# PSoC_Connections.net
KiCad netlist of a schematic drawn in Altium Designer
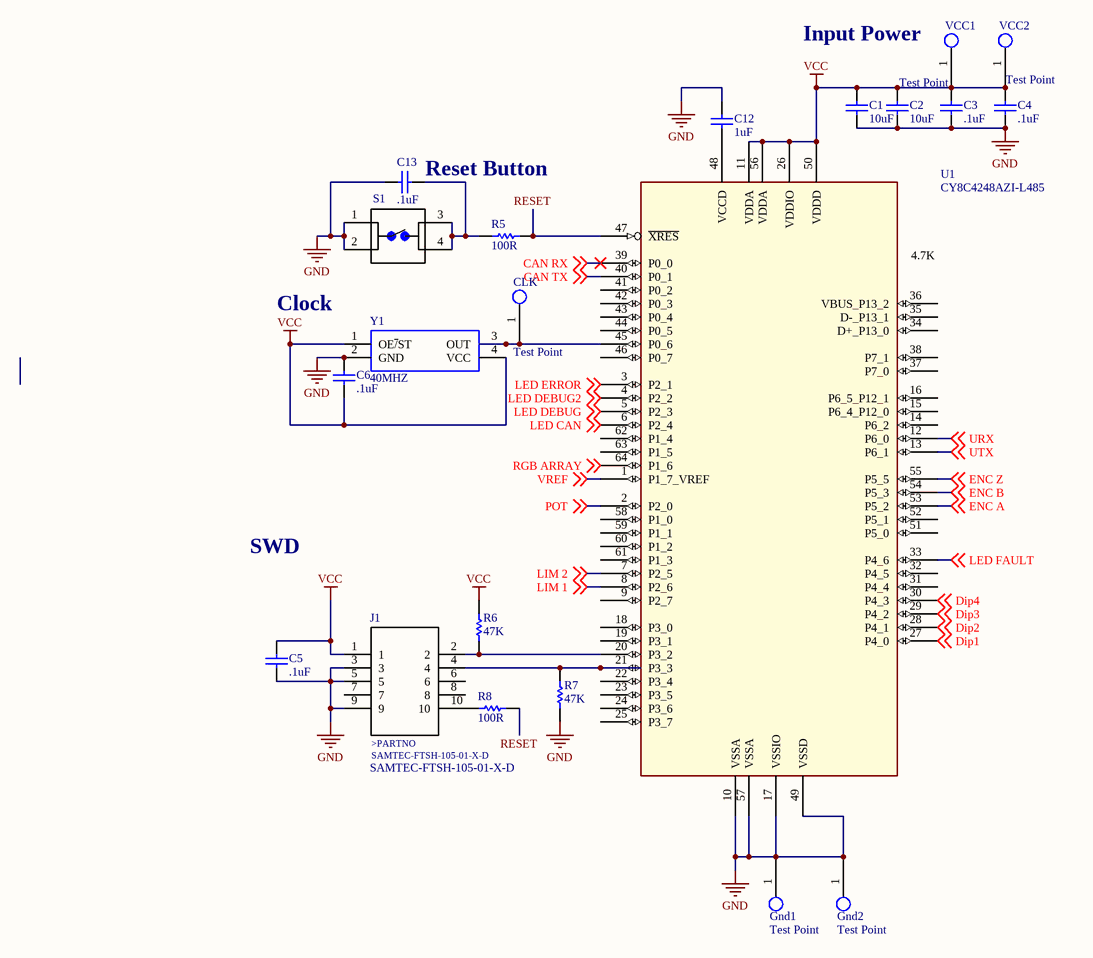
[diagram p0: PSoC Connections.SchDoc]

(export (version "E")
  (design (tool "Eeschema 10.0.6"))
  (components
    (comp (ref "C1")
      (value "10uF")
      (footprint "CAPC0805(2012)130_N")
      (description "CAP 390pF 200V ±5% 0805 (2012 Metric) Thickness 1.3mm SMD")
      (fields (field (name "TOLERANCE") "Â±5%"))
      (libsource (lib "Altium Content Vault") (part "CAP"))
    )
    (comp (ref "C2")
      (value "10uF")
      (footprint "CAPC0805(2012)130_N")
      (description "CAP 390pF 200V ±5% 0805 (2012 Metric) Thickness 1.3mm SMD")
      (fields (field (name "TOLERANCE") "Â±5%"))
      (libsource (lib "Altium Content Vault") (part "CAP"))
    )
    (comp (ref "C3")
      (value ".1uF")
      (footprint "CAPC0805(2012)130_N")
      (description "CAP 390pF 200V ±5% 0805 (2012 Metric) Thickness 1.3mm SMD")
      (fields (field (name "TOLERANCE") "Â±5%"))
      (libsource (lib "Altium Content Vault") (part "CAP"))
    )
    (comp (ref "C4")
      (value ".1uF")
      (footprint "CAPC0805(2012)130_N")
      (description "CAP 390pF 200V ±5% 0805 (2012 Metric) Thickness 1.3mm SMD")
      (fields (field (name "TOLERANCE") "Â±5%"))
      (libsource (lib "Altium Content Vault") (part "CAP"))
    )
    (comp (ref "C5")
      (value ".1uF")
      (footprint "CAPC0805(2012)130_N")
      (description "CAP 390pF 200V ±5% 0805 (2012 Metric) Thickness 1.3mm SMD")
      (fields (field (name "TOLERANCE") "Â±5%"))
      (libsource (lib "Altium Content Vault") (part "CAP"))
    )
    (comp (ref "C6")
      (value ".1uF")
      (footprint "CAPC0805(2012)130_N")
      (description "CAP 390pF 200V ±5% 0805 (2012 Metric) Thickness 1.3mm SMD")
      (fields (field (name "TOLERANCE") "Â±5%"))
      (libsource (lib "Altium Content Vault") (part "CAP"))
    )
    (comp (ref "C12")
      (value "1uF")
      (footprint "CAPC0805(2012)130_N")
      (description "CAP 390pF 200V ±5% 0805 (2012 Metric) Thickness 1.3mm SMD")
      (fields (field (name "TOLERANCE") "Â±5%"))
      (libsource (lib "Altium Content Vault") (part "CAP"))
    )
    (comp (ref "C13")
      (value ".1uF")
      (footprint "CAPC0805(2012)130_N")
      (description "CAP 390pF 200V ±5% 0805 (2012 Metric) Thickness 1.3mm SMD")
      (fields (field (name "TOLERANCE") "Â±5%"))
      (libsource (lib "Altium Content Vault") (part "CAP"))
    )
    (comp (ref "CLK")
      (value "Test Point")
      (footprint "Test Point Through-hole")
      (libsource (lib "Husky Robotics Standard Library 2019-2020") (part "Test Point"))
    )
    (comp (ref "Gnd1")
      (value "Test Point")
      (footprint "Test Point Through-hole")
      (libsource (lib "Husky Robotics Standard Library 2019-2020") (part "Test Point"))
    )
    (comp (ref "Gnd2")
      (value "Test Point")
      (footprint "Test Point Through-hole")
      (libsource (lib "Husky Robotics Standard Library 2019-2020") (part "Test Point"))
    )
    (comp (ref "J1")
      (value "SAMTEC-FTSH-105-01-X-D")
      (footprint "SAMTEC-FTSH-105-01-X-D")
      (libsource (lib "Husky Robotics Standard Library 2019-2020") (part "SAMTEC-FTSH-105-01-X-D"))
    )
    (comp (ref "R5")
      (value "100R")
      (footprint "RESC0805(2012)_N")
      (description "120R 0.125W 5% 0805 (2012 Metric)  SMD")
      (fields (field (name "TOLERANCE") "5 %") (field (name "POWER") "0.125 W"))
      (libsource (lib "Husky Robotics Standard Library 2019-2020") (part "120R 5% 0805"))
    )
    (comp (ref "R6")
      (value "47K")
      (footprint "RESC0805(2012)_N")
      (description "4.7K")
      (fields (field (name "TOLERANCE") "5 %") (field (name "POWER") "0.125 W"))
      (libsource (lib "Husky Robotics Standard Library 2019-2020") (part "120R 5% 0805"))
    )
    (comp (ref "R7")
      (value "47K")
      (footprint "RESC0805(2012)_N")
      (description "120R 0.125W 5% 0805 (2012 Metric)  SMD")
      (fields (field (name "TOLERANCE") "5 %") (field (name "POWER") "0.125 W"))
      (libsource (lib "Husky Robotics Standard Library 2019-2020") (part "120R 5% 0805"))
    )
    (comp (ref "R8")
      (value "100R")
      (footprint "RESC0805(2012)_N")
      (description "120R 0.125W 5% 0805 (2012 Metric)  SMD")
      (fields (field (name "TOLERANCE") "5 %") (field (name "POWER") "0.125 W"))
      (libsource (lib "Husky Robotics Standard Library 2019-2020") (part "120R 5% 0805"))
    )
    (comp (ref "S1")
      (value "1825910-7")
      (footprint "Switch 6mm 24V (NO)")
      (description "FSM4JAH=6MM TACT SWITCH, HIGH TEMP")
      (fields (field (name "MF") "TE Connectivity") (field (name "DIGI-KEY_PART_NUMBER") "450-1804-ND"))
      (libsource (lib "Husky Robotics Standard Library 2019-2020") (part "Switch 6mm 24V (NO)"))
    )
    (comp (ref "U1")
      (value "CY8C4248AZI-L485")
      (footprint "TQFP50P1200X1200X160-64N")
      (libsource (lib "Husky Robotics Standard Library 2019-2020") (part "CY8C4248AZI-L485"))
    )
    (comp (ref "VCC1")
      (value "Test Point")
      (footprint "Test Point Through-hole")
      (libsource (lib "Husky Robotics Standard Library 2019-2020") (part "Test Point"))
    )
    (comp (ref "VCC2")
      (value "Test Point")
      (footprint "Test Point Through-hole")
      (libsource (lib "Husky Robotics Standard Library 2019-2020") (part "Test Point"))
    )
    (comp (ref "Y1")
      (value "40MHZ")
      (footprint "SG-636")
      (description "Standard Clock Oscillators 50MHz 3.3Volt 100ppm -20C +70C")
      (fields (field (name "MANUFACTURER_PART_NUMBER") "SG-636PCW 50.0000MC3: ROHS"))
      (libsource (lib "Husky Robotics Standard Library 2019-2020") (part "SG-636"))
    )
  )
  (nets
    (net (code "1") (name "/RESET") (class "Default")
      (node (ref "R5") (pin "2") (pinfunction "2_2") (pintype "passive"))
      (node (ref "R8") (pin "2") (pinfunction "2_2") (pintype "passive"))
      (node (ref "U1") (pin "47") (pinfunction "~{XRES}_47") (pintype "input"))
    )
    (net (code "2") (name "CAN RX") (class "Default")
      (node (ref "U1") (pin "39") (pinfunction "P0_0_39") (pintype "bidirectional"))
    )
    (net (code "3") (name "CAN TX") (class "Default")
      (node (ref "U1") (pin "40") (pinfunction "P0_1_40") (pintype "bidirectional"))
    )
    (net (code "4") (name "Dip1") (class "Default")
      (node (ref "U1") (pin "27") (pinfunction "P4_0_27") (pintype "bidirectional"))
    )
    (net (code "5") (name "Dip2") (class "Default")
      (node (ref "U1") (pin "28") (pinfunction "P4_1_28") (pintype "bidirectional"))
    )
    (net (code "6") (name "Dip3") (class "Default")
      (node (ref "U1") (pin "29") (pinfunction "P4_2_29") (pintype "bidirectional"))
    )
    (net (code "7") (name "Dip4") (class "Default")
      (node (ref "U1") (pin "30") (pinfunction "P4_3_30") (pintype "bidirectional"))
    )
    (net (code "8") (name "ENC A") (class "Default")
      (node (ref "U1") (pin "53") (pinfunction "P5_2_53") (pintype "bidirectional"))
    )
    (net (code "9") (name "ENC B") (class "Default")
      (node (ref "U1") (pin "54") (pinfunction "P5_3_54") (pintype "bidirectional"))
    )
    (net (code "10") (name "ENC Z") (class "Default")
      (node (ref "U1") (pin "55") (pinfunction "P5_5_55") (pintype "bidirectional"))
    )
    (net (code "11") (name "GND") (class "Default")
      (node (ref "C1") (pin "1") (pinfunction "1_1") (pintype "passive"))
      (node (ref "C12") (pin "2") (pinfunction "2_2") (pintype "passive"))
      (node (ref "C13") (pin "2") (pinfunction "2_2") (pintype "passive"))
      (node (ref "C2") (pin "1") (pinfunction "1_1") (pintype "passive"))
      (node (ref "C3") (pin "1") (pinfunction "1_1") (pintype "passive"))
      (node (ref "C4") (pin "1") (pinfunction "1_1") (pintype "passive"))
      (node (ref "C5") (pin "1") (pinfunction "1_1") (pintype "passive"))
      (node (ref "C6") (pin "2") (pinfunction "2_2") (pintype "passive"))
      (node (ref "Gnd1") (pin "1") (pinfunction "1_1") (pintype "passive"))
      (node (ref "Gnd2") (pin "1") (pinfunction "1_1") (pintype "passive"))
      (node (ref "J1") (pin "3") (pinfunction "3_3") (pintype "passive"))
      (node (ref "J1") (pin "5") (pinfunction "5_5") (pintype "passive"))
      (node (ref "J1") (pin "9") (pinfunction "9_9") (pintype "passive"))
      (node (ref "R7") (pin "1") (pinfunction "1_1") (pintype "passive"))
      (node (ref "S1") (pin "1") (pinfunction "1_1") (pintype "passive"))
      (node (ref "S1") (pin "2") (pinfunction "2_2") (pintype "passive"))
      (node (ref "U1") (pin "10") (pinfunction "VSSA_10") (pintype "power_in"))
      (node (ref "U1") (pin "17") (pinfunction "VSSIO_17") (pintype "power_in"))
      (node (ref "U1") (pin "49") (pinfunction "VSSD_49") (pintype "power_in"))
      (node (ref "U1") (pin "57") (pinfunction "VSSA_57") (pintype "power_in"))
      (node (ref "Y1") (pin "2") (pinfunction "GND_2") (pintype "passive"))
    )
    (net (code "12") (name "LED CAN") (class "Default")
      (node (ref "U1") (pin "6") (pinfunction "P2_4_6") (pintype "bidirectional"))
    )
    (net (code "13") (name "LED DEBUG") (class "Default")
      (node (ref "U1") (pin "5") (pinfunction "P2_3_5") (pintype "bidirectional"))
    )
    (net (code "14") (name "LED DEBUG2") (class "Default")
      (node (ref "U1") (pin "4") (pinfunction "P2_2_4") (pintype "bidirectional"))
    )
    (net (code "15") (name "LED ERROR") (class "Default")
      (node (ref "U1") (pin "3") (pinfunction "P2_1_3") (pintype "bidirectional"))
    )
    (net (code "16") (name "LED FAULT") (class "Default")
      (node (ref "U1") (pin "33") (pinfunction "P4_6_33") (pintype "bidirectional"))
    )
    (net (code "17") (name "LIM 1") (class "Default")
      (node (ref "U1") (pin "8") (pinfunction "P2_6_8") (pintype "bidirectional"))
    )
    (net (code "18") (name "LIM 2") (class "Default")
      (node (ref "U1") (pin "7") (pinfunction "P2_5_7") (pintype "bidirectional"))
    )
    (net (code "19") (name "Net-(C13-Pad1)") (class "Default")
      (node (ref "C13") (pin "1") (pinfunction "1_1") (pintype "passive"))
      (node (ref "R5") (pin "1") (pinfunction "1_1") (pintype "passive"))
      (node (ref "S1") (pin "3") (pinfunction "3_3") (pintype "passive"))
      (node (ref "S1") (pin "4") (pinfunction "4_4") (pintype "passive"))
    )
    (net (code "20") (name "Net-(J1-Pad10)") (class "Default")
      (node (ref "J1") (pin "10") (pinfunction "10_10") (pintype "passive"))
      (node (ref "R8") (pin "1") (pinfunction "1_1") (pintype "passive"))
    )
    (net (code "21") (name "Net-(U1-P0_6)") (class "Default")
      (node (ref "CLK") (pin "1") (pinfunction "1_1") (pintype "passive"))
      (node (ref "U1") (pin "45") (pinfunction "P0_6_45") (pintype "bidirectional"))
      (node (ref "Y1") (pin "3") (pinfunction "OUT_3") (pintype "passive"))
    )
    (net (code "22") (name "Net-(U1-P3_2)") (class "Default")
      (node (ref "J1") (pin "2") (pinfunction "2_2") (pintype "passive"))
      (node (ref "R6") (pin "1") (pinfunction "1_1") (pintype "passive"))
      (node (ref "U1") (pin "20") (pinfunction "P3_2_20") (pintype "bidirectional"))
    )
    (net (code "23") (name "Net-(U1-P3_3)") (class "Default")
      (node (ref "J1") (pin "4") (pinfunction "4_4") (pintype "passive"))
      (node (ref "R7") (pin "2") (pinfunction "2_2") (pintype "passive"))
      (node (ref "U1") (pin "21") (pinfunction "P3_3_21") (pintype "bidirectional"))
    )
    (net (code "24") (name "Net-(U1-VCCD)") (class "Default")
      (node (ref "C12") (pin "1") (pinfunction "1_1") (pintype "passive"))
      (node (ref "U1") (pin "48") (pinfunction "VCCD_48") (pintype "power_in"))
    )
    (net (code "25") (name "POT") (class "Default")
      (node (ref "U1") (pin "2") (pinfunction "P2_0_2") (pintype "bidirectional"))
    )
    (net (code "26") (name "RGB ARRAY") (class "Default")
      (node (ref "U1") (pin "64") (pinfunction "P1_6_64") (pintype "bidirectional"))
    )
    (net (code "27") (name "URX") (class "Default")
      (node (ref "U1") (pin "12") (pinfunction "P6_0_12") (pintype "bidirectional"))
    )
    (net (code "28") (name "UTX") (class "Default")
      (node (ref "U1") (pin "13") (pinfunction "P6_1_13") (pintype "bidirectional"))
    )
    (net (code "29") (name "VCC") (class "Default")
      (node (ref "C1") (pin "2") (pinfunction "2_2") (pintype "passive"))
      (node (ref "C2") (pin "2") (pinfunction "2_2") (pintype "passive"))
      (node (ref "C3") (pin "2") (pinfunction "2_2") (pintype "passive"))
      (node (ref "C4") (pin "2") (pinfunction "2_2") (pintype "passive"))
      (node (ref "C5") (pin "2") (pinfunction "2_2") (pintype "passive"))
      (node (ref "C6") (pin "1") (pinfunction "1_1") (pintype "passive"))
      (node (ref "J1") (pin "1") (pinfunction "1_1") (pintype "passive"))
      (node (ref "R6") (pin "2") (pinfunction "2_2") (pintype "passive"))
      (node (ref "U1") (pin "11") (pinfunction "VDDA_11") (pintype "power_in"))
      (node (ref "U1") (pin "26") (pinfunction "VDDIO_26") (pintype "power_in"))
      (node (ref "U1") (pin "50") (pinfunction "VDDD_50") (pintype "power_in"))
      (node (ref "U1") (pin "56") (pinfunction "VDDA_56") (pintype "power_in"))
      (node (ref "VCC1") (pin "1") (pinfunction "1_1") (pintype "passive"))
      (node (ref "VCC2") (pin "1") (pinfunction "1_1") (pintype "passive"))
      (node (ref "Y1") (pin "1") (pinfunction "OE~{/}ST_1") (pintype "passive"))
      (node (ref "Y1") (pin "4") (pinfunction "VCC_4") (pintype "power_in"))
    )
    (net (code "30") (name "VREF") (class "Default")
      (node (ref "U1") (pin "1") (pinfunction "P1_7_VREF_1") (pintype "bidirectional"))
    )
    (net (code "31") (name "unconnected-(J1-Pad6)") (class "Default")
      (node (ref "J1") (pin "6") (pinfunction "6_6") (pintype "passive"))
    )
    (net (code "32") (name "unconnected-(J1-Pad7)") (class "Default")
      (node (ref "J1") (pin "7") (pinfunction "7_7") (pintype "passive"))
    )
    (net (code "33") (name "unconnected-(J1-Pad8)") (class "Default")
      (node (ref "J1") (pin "8") (pinfunction "8_8") (pintype "passive"))
    )
    (net (code "34") (name "unconnected-(U1-D+_P13_0-Pad34)") (class "Default")
      (node (ref "U1") (pin "34") (pinfunction "D+_P13_0_34") (pintype "bidirectional"))
    )
    (net (code "35") (name "unconnected-(U1-D-_P13_1-Pad35)") (class "Default")
      (node (ref "U1") (pin "35") (pinfunction "D-_P13_1_35") (pintype "bidirectional"))
    )
    (net (code "36") (name "unconnected-(U1-P0_2-Pad41)") (class "Default")
      (node (ref "U1") (pin "41") (pinfunction "P0_2_41") (pintype "bidirectional"))
    )
    (net (code "37") (name "unconnected-(U1-P0_3-Pad42)") (class "Default")
      (node (ref "U1") (pin "42") (pinfunction "P0_3_42") (pintype "bidirectional"))
    )
    (net (code "38") (name "unconnected-(U1-P0_4-Pad43)") (class "Default")
      (node (ref "U1") (pin "43") (pinfunction "P0_4_43") (pintype "bidirectional"))
    )
    (net (code "39") (name "unconnected-(U1-P0_5-Pad44)") (class "Default")
      (node (ref "U1") (pin "44") (pinfunction "P0_5_44") (pintype "bidirectional"))
    )
    (net (code "40") (name "unconnected-(U1-P0_7-Pad46)") (class "Default")
      (node (ref "U1") (pin "46") (pinfunction "P0_7_46") (pintype "bidirectional"))
    )
    (net (code "41") (name "unconnected-(U1-P1_0-Pad58)") (class "Default")
      (node (ref "U1") (pin "58") (pinfunction "P1_0_58") (pintype "bidirectional"))
    )
    (net (code "42") (name "unconnected-(U1-P1_1-Pad59)") (class "Default")
      (node (ref "U1") (pin "59") (pinfunction "P1_1_59") (pintype "bidirectional"))
    )
    (net (code "43") (name "unconnected-(U1-P1_2-Pad60)") (class "Default")
      (node (ref "U1") (pin "60") (pinfunction "P1_2_60") (pintype "bidirectional"))
    )
    (net (code "44") (name "unconnected-(U1-P1_3-Pad61)") (class "Default")
      (node (ref "U1") (pin "61") (pinfunction "P1_3_61") (pintype "bidirectional"))
    )
    (net (code "45") (name "unconnected-(U1-P1_4-Pad62)") (class "Default")
      (node (ref "U1") (pin "62") (pinfunction "P1_4_62") (pintype "bidirectional"))
    )
    (net (code "46") (name "unconnected-(U1-P1_5-Pad63)") (class "Default")
      (node (ref "U1") (pin "63") (pinfunction "P1_5_63") (pintype "bidirectional"))
    )
    (net (code "47") (name "unconnected-(U1-P2_7-Pad9)") (class "Default")
      (node (ref "U1") (pin "9") (pinfunction "P2_7_9") (pintype "bidirectional"))
    )
    (net (code "48") (name "unconnected-(U1-P3_0-Pad18)") (class "Default")
      (node (ref "U1") (pin "18") (pinfunction "P3_0_18") (pintype "bidirectional"))
    )
    (net (code "49") (name "unconnected-(U1-P3_1-Pad19)") (class "Default")
      (node (ref "U1") (pin "19") (pinfunction "P3_1_19") (pintype "bidirectional"))
    )
    (net (code "50") (name "unconnected-(U1-P3_4-Pad22)") (class "Default")
      (node (ref "U1") (pin "22") (pinfunction "P3_4_22") (pintype "bidirectional"))
    )
    (net (code "51") (name "unconnected-(U1-P3_5-Pad23)") (class "Default")
      (node (ref "U1") (pin "23") (pinfunction "P3_5_23") (pintype "bidirectional"))
    )
    (net (code "52") (name "unconnected-(U1-P3_6-Pad24)") (class "Default")
      (node (ref "U1") (pin "24") (pinfunction "P3_6_24") (pintype "bidirectional"))
    )
    (net (code "53") (name "unconnected-(U1-P3_7-Pad25)") (class "Default")
      (node (ref "U1") (pin "25") (pinfunction "P3_7_25") (pintype "bidirectional"))
    )
    (net (code "54") (name "unconnected-(U1-P4_4-Pad31)") (class "Default")
      (node (ref "U1") (pin "31") (pinfunction "P4_4_31") (pintype "bidirectional"))
    )
    (net (code "55") (name "unconnected-(U1-P4_5-Pad32)") (class "Default")
      (node (ref "U1") (pin "32") (pinfunction "P4_5_32") (pintype "bidirectional"))
    )
    (net (code "56") (name "unconnected-(U1-P5_0-Pad51)") (class "Default")
      (node (ref "U1") (pin "51") (pinfunction "P5_0_51") (pintype "bidirectional"))
    )
    (net (code "57") (name "unconnected-(U1-P5_1-Pad52)") (class "Default")
      (node (ref "U1") (pin "52") (pinfunction "P5_1_52") (pintype "bidirectional"))
    )
    (net (code "58") (name "unconnected-(U1-P6_2-Pad14)") (class "Default")
      (node (ref "U1") (pin "14") (pinfunction "P6_2_14") (pintype "bidirectional"))
    )
    (net (code "59") (name "unconnected-(U1-P6_4_P12_0-Pad15)") (class "Default")
      (node (ref "U1") (pin "15") (pinfunction "P6_4_P12_0_15") (pintype "bidirectional"))
    )
    (net (code "60") (name "unconnected-(U1-P6_5_P12_1-Pad16)") (class "Default")
      (node (ref "U1") (pin "16") (pinfunction "P6_5_P12_1_16") (pintype "bidirectional"))
    )
    (net (code "61") (name "unconnected-(U1-P7_0-Pad37)") (class "Default")
      (node (ref "U1") (pin "37") (pinfunction "P7_0_37") (pintype "bidirectional"))
    )
    (net (code "62") (name "unconnected-(U1-P7_1-Pad38)") (class "Default")
      (node (ref "U1") (pin "38") (pinfunction "P7_1_38") (pintype "bidirectional"))
    )
    (net (code "63") (name "unconnected-(U1-VBUS_P13_2-Pad36)") (class "Default")
      (node (ref "U1") (pin "36") (pinfunction "VBUS_P13_2_36") (pintype "bidirectional"))
    )
  )
)
